# 10_USB_HDMI.net
KiCad netlist of a schematic drawn in Altium Designer
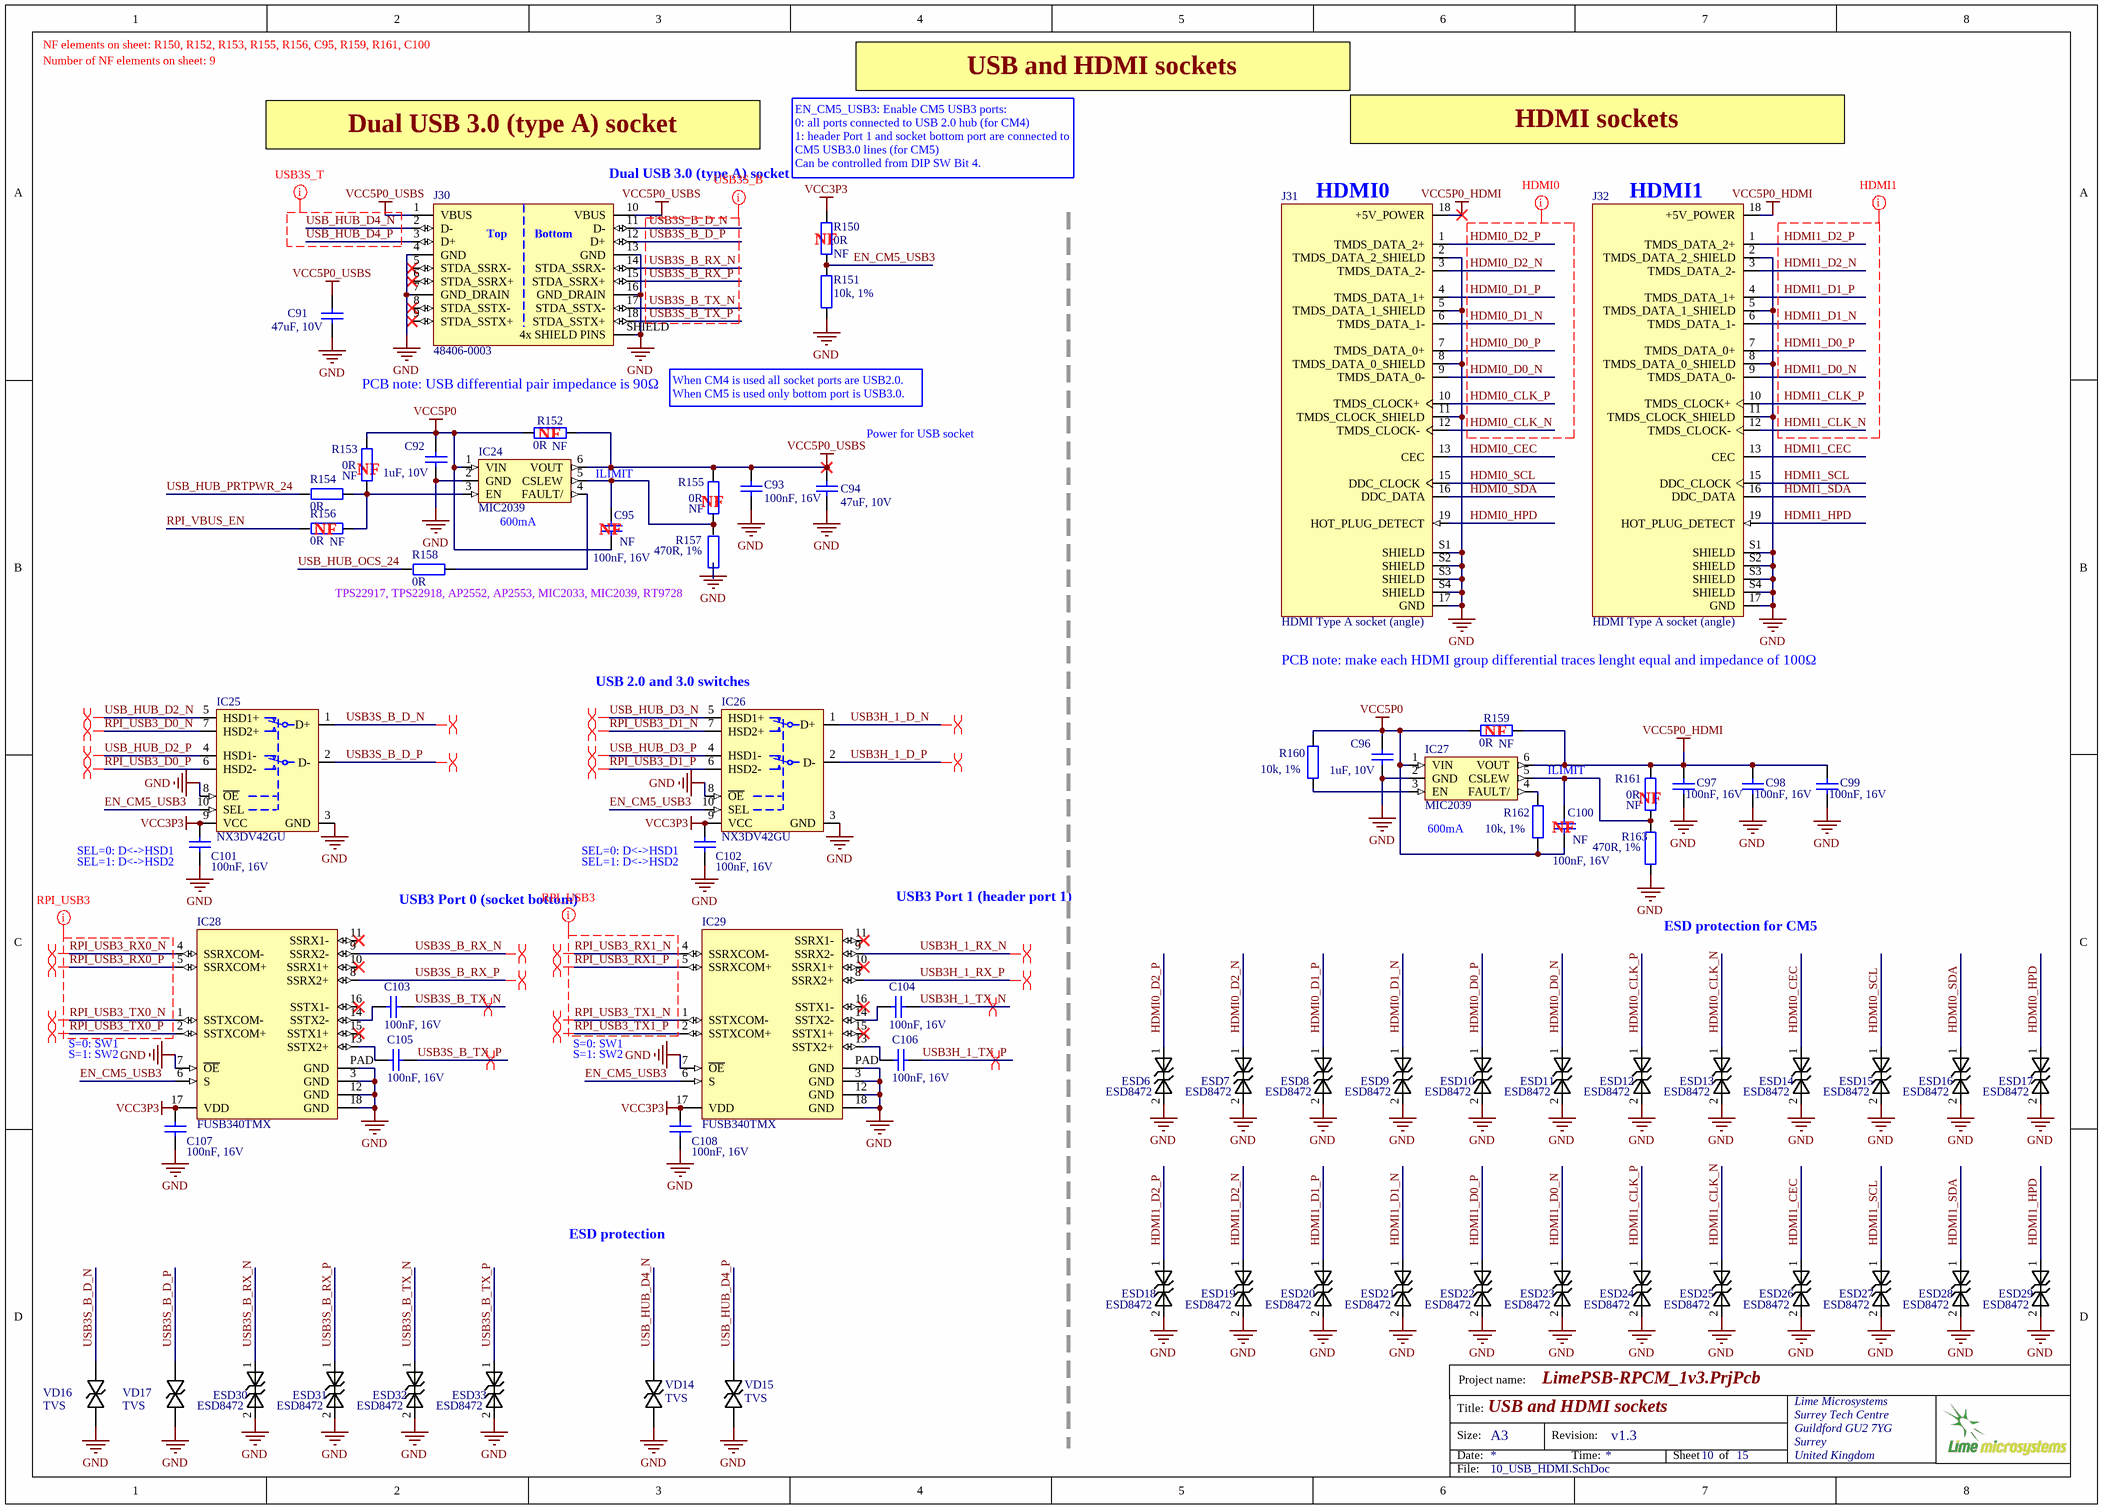
[diagram p0: 10_USB_HDMI.SchDoc]

(export (version "E")
  (design (tool "Eeschema 10.0.6"))
  (components
    (comp (ref "C91")
      (value "47uF, 10V")
      (footprint "CAP1206")
      (fields (field (name "TOLERANCE") "±20%") (field (name "MANUFACTURER") "TDK Corporation"))
      (libsource (lib "LimeFPGAboard_schLib") (part "Cap_1206"))
    )
    (comp (ref "C92")
      (value "1uF, 10V")
      (footprint "CAP0402")
      (fields (field (name "MANUFACTURER") "Yageo"))
      (libsource (lib "LimeMicroAltiumLib_schLib") (part "Cap_0402"))
    )
    (comp (ref "C93")
      (value "100nF, 16V")
      (footprint "CAP0402")
      (fields
        (field (name "MANUFACTURER") "Murata Electronics")
        (field (name "TOLERANCE") "10 %")
        (field (name "MANUFACTURER PART NUMBER") "GRM155R71C104KA88D")
      )
      (libsource (lib "LimeMicroAltiumLib_schLib") (part "Cap_0402"))
    )
    (comp (ref "C94")
      (value "47uF, 10V")
      (footprint "CAP1206")
      (fields (field (name "TOLERANCE") "±20%") (field (name "MANUFACTURER") "TDK Corporation"))
      (libsource (lib "LimeFPGAboard_schLib") (part "Cap_1206"))
    )
    (comp (ref "C95")
      (value "100nF, 16V")
      (footprint "CAP0402")
      (fields
        (field (name "ASSEMBLY INFO") "NF")
        (field (name "MANUFACTURER") "Murata Electronics")
        (field (name "TOLERANCE") "10 %")
        (field (name "MANUFACTURER PART NUMBER") "GRM155R71C104KA88D")
      )
      (libsource (lib "LimeMicroAltiumLib_schLib") (part "Cap_0402"))
    )
    (comp (ref "C96")
      (value "1uF, 10V")
      (footprint "CAP0402")
      (fields (field (name "MANUFACTURER") "Yageo"))
      (libsource (lib "LimeMicroAltiumLib_schLib") (part "Cap_0402"))
    )
    (comp (ref "C97")
      (value "100nF, 16V")
      (footprint "CAP0402")
      (fields
        (field (name "MANUFACTURER") "Murata Electronics")
        (field (name "TOLERANCE") "10 %")
        (field (name "MANUFACTURER PART NUMBER") "GRM155R71C104KA88D")
      )
      (libsource (lib "LimeMicroAltiumLib_schLib") (part "Cap_0402"))
    )
    (comp (ref "C98")
      (value "100nF, 16V")
      (footprint "CAP0402")
      (fields
        (field (name "MANUFACTURER") "Murata Electronics")
        (field (name "TOLERANCE") "10 %")
        (field (name "MANUFACTURER PART NUMBER") "GRM155R71C104KA88D")
      )
      (libsource (lib "LimeMicroAltiumLib_schLib") (part "Cap_0402"))
    )
    (comp (ref "C99")
      (value "100nF, 16V")
      (footprint "CAP0402")
      (fields
        (field (name "MANUFACTURER") "Murata Electronics")
        (field (name "TOLERANCE") "10 %")
        (field (name "MANUFACTURER PART NUMBER") "GRM155R71C104KA88D")
      )
      (libsource (lib "LimeMicroAltiumLib_schLib") (part "Cap_0402"))
    )
    (comp (ref "C100")
      (value "100nF, 16V")
      (footprint "CAP0402")
      (fields
        (field (name "ASSEMBLY INFO") "NF")
        (field (name "MANUFACTURER") "Murata Electronics")
        (field (name "TOLERANCE") "10 %")
        (field (name "MANUFACTURER PART NUMBER") "GRM155R71C104KA88D")
      )
      (libsource (lib "LimeMicroAltiumLib_schLib") (part "Cap_0402"))
    )
    (comp (ref "C101")
      (value "100nF, 16V")
      (footprint "CAP0402")
      (fields
        (field (name "MANUFACTURER") "Murata Electronics")
        (field (name "TOLERANCE") "10 %")
        (field (name "MANUFACTURER PART NUMBER") "GRM155R71C104KA88D")
      )
      (libsource (lib "") (part "Cap_0402_1"))
    )
    (comp (ref "C102")
      (value "100nF, 16V")
      (footprint "CAP0402")
      (fields
        (field (name "MANUFACTURER") "Murata Electronics")
        (field (name "TOLERANCE") "10 %")
        (field (name "MANUFACTURER PART NUMBER") "GRM155R71C104KA88D")
      )
      (libsource (lib "") (part "Cap_0402_1"))
    )
    (comp (ref "C103")
      (value "100nF, 16V")
      (footprint "CAP0402")
      (fields
        (field (name "MANUFACTURER") "Murata Electronics")
        (field (name "TOLERANCE") "10 %")
        (field (name "MANUFACTURER PART NUMBER") "GRM155R71C104KA88D")
      )
      (libsource (lib "") (part "Cap_0402_1"))
    )
    (comp (ref "C104")
      (value "100nF, 16V")
      (footprint "CAP0402")
      (fields
        (field (name "MANUFACTURER") "Murata Electronics")
        (field (name "TOLERANCE") "10 %")
        (field (name "MANUFACTURER PART NUMBER") "GRM155R71C104KA88D")
      )
      (libsource (lib "") (part "Cap_0402_1"))
    )
    (comp (ref "C105")
      (value "100nF, 16V")
      (footprint "CAP0402")
      (fields
        (field (name "MANUFACTURER") "Murata Electronics")
        (field (name "TOLERANCE") "10 %")
        (field (name "MANUFACTURER PART NUMBER") "GRM155R71C104KA88D")
      )
      (libsource (lib "") (part "Cap_0402_1"))
    )
    (comp (ref "C106")
      (value "100nF, 16V")
      (footprint "CAP0402")
      (fields
        (field (name "MANUFACTURER") "Murata Electronics")
        (field (name "TOLERANCE") "10 %")
        (field (name "MANUFACTURER PART NUMBER") "GRM155R71C104KA88D")
      )
      (libsource (lib "") (part "Cap_0402_1"))
    )
    (comp (ref "C107")
      (value "100nF, 16V")
      (footprint "CAP0402")
      (fields
        (field (name "MANUFACTURER") "Murata Electronics")
        (field (name "TOLERANCE") "10 %")
        (field (name "MANUFACTURER PART NUMBER") "GRM155R71C104KA88D")
      )
      (libsource (lib "") (part "Cap_0402_1"))
    )
    (comp (ref "C108")
      (value "100nF, 16V")
      (footprint "CAP0402")
      (fields
        (field (name "MANUFACTURER") "Murata Electronics")
        (field (name "TOLERANCE") "10 %")
        (field (name "MANUFACTURER PART NUMBER") "GRM155R71C104KA88D")
      )
      (libsource (lib "") (part "Cap_0402_1"))
    )
    (comp (ref "ESD6")
      (value "ESD8472")
      (footprint "ESD8472_X3DFN2")
      (fields (field (name "MANUFACTURER") "ON Semiconductor"))
      (libsource (lib "LimeMicroAltiumLib_schLib") (part "ESD8472"))
    )
    (comp (ref "ESD7")
      (value "ESD8472")
      (footprint "ESD8472_X3DFN2")
      (fields (field (name "MANUFACTURER") "ON Semiconductor"))
      (libsource (lib "LimeMicroAltiumLib_schLib") (part "ESD8472"))
    )
    (comp (ref "ESD8")
      (value "ESD8472")
      (footprint "ESD8472_X3DFN2")
      (fields (field (name "MANUFACTURER") "ON Semiconductor"))
      (libsource (lib "LimeMicroAltiumLib_schLib") (part "ESD8472"))
    )
    (comp (ref "ESD9")
      (value "ESD8472")
      (footprint "ESD8472_X3DFN2")
      (fields (field (name "MANUFACTURER") "ON Semiconductor"))
      (libsource (lib "LimeMicroAltiumLib_schLib") (part "ESD8472"))
    )
    (comp (ref "ESD10")
      (value "ESD8472")
      (footprint "ESD8472_X3DFN2")
      (fields (field (name "MANUFACTURER") "ON Semiconductor"))
      (libsource (lib "LimeMicroAltiumLib_schLib") (part "ESD8472"))
    )
    (comp (ref "ESD11")
      (value "ESD8472")
      (footprint "ESD8472_X3DFN2")
      (fields (field (name "MANUFACTURER") "ON Semiconductor"))
      (libsource (lib "LimeMicroAltiumLib_schLib") (part "ESD8472"))
    )
    (comp (ref "ESD12")
      (value "ESD8472")
      (footprint "ESD8472_X3DFN2")
      (fields (field (name "MANUFACTURER") "ON Semiconductor"))
      (libsource (lib "LimeMicroAltiumLib_schLib") (part "ESD8472"))
    )
    (comp (ref "ESD13")
      (value "ESD8472")
      (footprint "ESD8472_X3DFN2")
      (fields (field (name "MANUFACTURER") "ON Semiconductor"))
      (libsource (lib "LimeMicroAltiumLib_schLib") (part "ESD8472"))
    )
    (comp (ref "ESD14")
      (value "ESD8472")
      (footprint "ESD8472_X3DFN2")
      (fields (field (name "MANUFACTURER") "ON Semiconductor"))
      (libsource (lib "LimeMicroAltiumLib_schLib") (part "ESD8472"))
    )
    (comp (ref "ESD15")
      (value "ESD8472")
      (footprint "ESD8472_X3DFN2")
      (fields (field (name "MANUFACTURER") "ON Semiconductor"))
      (libsource (lib "LimeMicroAltiumLib_schLib") (part "ESD8472"))
    )
    (comp (ref "ESD16")
      (value "ESD8472")
      (footprint "ESD8472_X3DFN2")
      (fields (field (name "MANUFACTURER") "ON Semiconductor"))
      (libsource (lib "LimeMicroAltiumLib_schLib") (part "ESD8472"))
    )
    (comp (ref "ESD17")
      (value "ESD8472")
      (footprint "ESD8472_X3DFN2")
      (fields (field (name "MANUFACTURER") "ON Semiconductor"))
      (libsource (lib "LimeMicroAltiumLib_schLib") (part "ESD8472"))
    )
    (comp (ref "ESD18")
      (value "ESD8472")
      (footprint "ESD8472_X3DFN2")
      (fields (field (name "MANUFACTURER") "ON Semiconductor"))
      (libsource (lib "LimeMicroAltiumLib_schLib") (part "ESD8472"))
    )
    (comp (ref "ESD19")
      (value "ESD8472")
      (footprint "ESD8472_X3DFN2")
      (fields (field (name "MANUFACTURER") "ON Semiconductor"))
      (libsource (lib "LimeMicroAltiumLib_schLib") (part "ESD8472"))
    )
    (comp (ref "ESD20")
      (value "ESD8472")
      (footprint "ESD8472_X3DFN2")
      (fields (field (name "MANUFACTURER") "ON Semiconductor"))
      (libsource (lib "LimeMicroAltiumLib_schLib") (part "ESD8472"))
    )
    (comp (ref "ESD21")
      (value "ESD8472")
      (footprint "ESD8472_X3DFN2")
      (fields (field (name "MANUFACTURER") "ON Semiconductor"))
      (libsource (lib "LimeMicroAltiumLib_schLib") (part "ESD8472"))
    )
    (comp (ref "ESD22")
      (value "ESD8472")
      (footprint "ESD8472_X3DFN2")
      (fields (field (name "MANUFACTURER") "ON Semiconductor"))
      (libsource (lib "LimeMicroAltiumLib_schLib") (part "ESD8472"))
    )
    (comp (ref "ESD23")
      (value "ESD8472")
      (footprint "ESD8472_X3DFN2")
      (fields (field (name "MANUFACTURER") "ON Semiconductor"))
      (libsource (lib "LimeMicroAltiumLib_schLib") (part "ESD8472"))
    )
    (comp (ref "ESD24")
      (value "ESD8472")
      (footprint "ESD8472_X3DFN2")
      (fields (field (name "MANUFACTURER") "ON Semiconductor"))
      (libsource (lib "LimeMicroAltiumLib_schLib") (part "ESD8472"))
    )
    (comp (ref "ESD25")
      (value "ESD8472")
      (footprint "ESD8472_X3DFN2")
      (fields (field (name "MANUFACTURER") "ON Semiconductor"))
      (libsource (lib "LimeMicroAltiumLib_schLib") (part "ESD8472"))
    )
    (comp (ref "ESD26")
      (value "ESD8472")
      (footprint "ESD8472_X3DFN2")
      (fields (field (name "MANUFACTURER") "ON Semiconductor"))
      (libsource (lib "LimeMicroAltiumLib_schLib") (part "ESD8472"))
    )
    (comp (ref "ESD27")
      (value "ESD8472")
      (footprint "ESD8472_X3DFN2")
      (fields (field (name "MANUFACTURER") "ON Semiconductor"))
      (libsource (lib "LimeMicroAltiumLib_schLib") (part "ESD8472"))
    )
    (comp (ref "ESD28")
      (value "ESD8472")
      (footprint "ESD8472_X3DFN2")
      (fields (field (name "MANUFACTURER") "ON Semiconductor"))
      (libsource (lib "LimeMicroAltiumLib_schLib") (part "ESD8472"))
    )
    (comp (ref "ESD29")
      (value "ESD8472")
      (footprint "ESD8472_X3DFN2")
      (fields (field (name "MANUFACTURER") "ON Semiconductor"))
      (libsource (lib "LimeMicroAltiumLib_schLib") (part "ESD8472"))
    )
    (comp (ref "ESD30")
      (value "ESD8472")
      (footprint "ESD8472_X3DFN2")
      (fields (field (name "MANUFACTURER") "ON Semiconductor"))
      (libsource (lib "LimeMicroAltiumLib_schLib") (part "ESD8472"))
    )
    (comp (ref "ESD31")
      (value "ESD8472")
      (footprint "ESD8472_X3DFN2")
      (fields (field (name "MANUFACTURER") "ON Semiconductor"))
      (libsource (lib "LimeMicroAltiumLib_schLib") (part "ESD8472"))
    )
    (comp (ref "ESD32")
      (value "ESD8472")
      (footprint "ESD8472_X3DFN2")
      (fields (field (name "MANUFACTURER") "ON Semiconductor"))
      (libsource (lib "LimeMicroAltiumLib_schLib") (part "ESD8472"))
    )
    (comp (ref "ESD33")
      (value "ESD8472")
      (footprint "ESD8472_X3DFN2")
      (fields (field (name "MANUFACTURER") "ON Semiconductor"))
      (libsource (lib "LimeMicroAltiumLib_schLib") (part "ESD8472"))
    )
    (comp (ref "IC24")
      (value "MIC2039")
      (footprint "SOT23-6")
      (fields (field (name "MANUFACTURER") "Microchip"))
      (libsource (lib "LimeMicroAltiumLib_schLib_r04") (part "MIC2033_power_switch"))
    )
    (comp (ref "IC25")
      (value "NX3DV42GU")
      (footprint "FSUSB42UMX")
      (fields (field (name "MANUFACTURER") "NXP Semiconductors"))
      (libsource (lib "LimeMicroAltiumLib_schLib_r01") (part "FSUSB42UMX"))
    )
    (comp (ref "IC26")
      (value "NX3DV42GU")
      (footprint "FSUSB42UMX")
      (fields (field (name "MANUFACTURER") "NXP Semiconductors"))
      (libsource (lib "LimeMicroAltiumLib_schLib_r01") (part "FSUSB42UMX"))
    )
    (comp (ref "IC27")
      (value "MIC2039")
      (footprint "SOT23-6")
      (fields (field (name "MANUFACTURER") "Microchip"))
      (libsource (lib "LimeMicroAltiumLib_schLib_r04") (part "MIC2033_power_switch"))
    )
    (comp (ref "IC28")
      (value "FUSB340TMX")
      (footprint "FUSB340TMX_USB_switch_18-XFQFN")
      (fields (field (name "MANUFACTURER") "ON Semiconductor / Fairchild"))
      (libsource (lib "LimeMicroAltiumLib") (part "FUSB340TMX_USB_switch"))
    )
    (comp (ref "IC29")
      (value "FUSB340TMX")
      (footprint "FUSB340TMX_USB_switch_18-XFQFN")
      (fields (field (name "MANUFACTURER") "ON Semiconductor / Fairchild"))
      (libsource (lib "LimeMicroAltiumLib") (part "FUSB340TMX_USB_switch"))
    )
    (comp (ref "J30")
      (value "48406-0003")
      (footprint "Dual_USB_48406-0003_Molex")
      (fields (field (name "MANUFACTURER") "Molex"))
      (libsource (lib "LimeMicroAltiumLib") (part "Dual_USB_48406-0003_Molex"))
    )
    (comp (ref "J31")
      (value "HDMI Type A socket (angle)")
      (footprint "HDMI_HD01-19-RA-TH")
      (fields (field (name "MANUFACTURER") "CUI Devices"))
      (libsource (lib "LimeMicroAltiumLib_schLib_r04") (part "HDMI_HD01-19-RA-TH"))
    )
    (comp (ref "J32")
      (value "HDMI Type A socket (angle)")
      (footprint "HDMI_HD01-19-RA-TH")
      (fields (field (name "MANUFACTURER") "CUI Devices"))
      (libsource (lib "LimeMicroAltiumLib_schLib_r04") (part "HDMI_HD01-19-RA-TH"))
    )
    (comp (ref "R150")
      (value "0R")
      (footprint "RES0402")
      (fields
        (field (name "ASSEMBLY INFO") "NF")
        (field (name "MANUFACTURER") "Yageo")
        (field (name "TOLERANCE") "Jumper")
      )
      (libsource (lib "") (part "Res_0402_1"))
    )
    (comp (ref "R151")
      (value "10k, 1%")
      (footprint "RES0402")
      (fields (field (name "MANUFACTURER") "Yageo") (field (name "TOLERANCE") "±1%"))
      (libsource (lib "") (part "Res_0402_1"))
    )
    (comp (ref "R152")
      (value "0R")
      (footprint "RES0402")
      (fields
        (field (name "ASSEMBLY INFO") "NF")
        (field (name "MANUFACTURER") "Yageo")
        (field (name "TOLERANCE") "Jumper")
      )
      (libsource (lib "LimeMicroAltiumLib_schLib") (part "Res_0402"))
    )
    (comp (ref "R153")
      (value "0R")
      (footprint "RES0402")
      (fields
        (field (name "ASSEMBLY INFO") "NF")
        (field (name "MANUFACTURER") "Yageo")
        (field (name "TOLERANCE") "Jumper")
      )
      (libsource (lib "LimeMicroAltiumLib_schLib") (part "Res_0402"))
    )
    (comp (ref "R154")
      (value "0R")
      (footprint "RES0402")
      (fields (field (name "MANUFACTURER") "Yageo") (field (name "TOLERANCE") "Jumper"))
      (libsource (lib "LimeMicroAltiumLib_schLib") (part "Res_0402"))
    )
    (comp (ref "R155")
      (value "0R")
      (footprint "RES0402")
      (fields
        (field (name "ASSEMBLY INFO") "NF")
        (field (name "MANUFACTURER") "Yageo")
        (field (name "TOLERANCE") "Jumper")
      )
      (libsource (lib "LimeMicroAltiumLib_schLib") (part "Res_0402"))
    )
    (comp (ref "R156")
      (value "0R")
      (footprint "RES0402")
      (fields
        (field (name "ASSEMBLY INFO") "NF")
        (field (name "MANUFACTURER") "Yageo")
        (field (name "TOLERANCE") "Jumper")
      )
      (libsource (lib "LimeMicroAltiumLib_schLib") (part "Res_0402"))
    )
    (comp (ref "R157")
      (value "470R, 1%")
      (footprint "RES0402")
      (fields (field (name "TOLERANCE") "1%") (field (name "MANUFACTURER") "Yageo"))
      (libsource (lib "LimeMicroAltiumLib_schLib") (part "Res_0402"))
    )
    (comp (ref "R158")
      (value "0R")
      (footprint "RES0402")
      (fields (field (name "MANUFACTURER") "Yageo") (field (name "TOLERANCE") "Jumper"))
      (libsource (lib "LimeMicroAltiumLib_schLib") (part "Res_0402"))
    )
    (comp (ref "R159")
      (value "0R")
      (footprint "RES0402")
      (fields
        (field (name "ASSEMBLY INFO") "NF")
        (field (name "MANUFACTURER") "Yageo")
        (field (name "TOLERANCE") "Jumper")
      )
      (libsource (lib "LimeMicroAltiumLib_schLib") (part "Res_0402"))
    )
    (comp (ref "R160")
      (value "10k, 1%")
      (footprint "RES0402")
      (fields (field (name "MANUFACTURER") "Yageo") (field (name "TOLERANCE") "±1%"))
      (libsource (lib "") (part "Res_0402_1"))
    )
    (comp (ref "R161")
      (value "0R")
      (footprint "RES0402")
      (fields
        (field (name "ASSEMBLY INFO") "NF")
        (field (name "MANUFACTURER") "Yageo")
        (field (name "TOLERANCE") "Jumper")
      )
      (libsource (lib "LimeMicroAltiumLib_schLib") (part "Res_0402"))
    )
    (comp (ref "R162")
      (value "10k, 1%")
      (footprint "RES0402")
      (fields (field (name "MANUFACTURER") "Yageo") (field (name "TOLERANCE") "±1%"))
      (libsource (lib "") (part "Res_0402_1"))
    )
    (comp (ref "R163")
      (value "470R, 1%")
      (footprint "RES0402")
      (fields (field (name "TOLERANCE") "1%") (field (name "MANUFACTURER") "Yageo"))
      (libsource (lib "LimeMicroAltiumLib_schLib") (part "Res_0402"))
    )
    (comp (ref "VD14")
      (value "TVS")
      (footprint "SOD323")
      (fields
        (field (name "MANUFACTURER PART NUMBER") "SD03LCC")
        (field (name "MANUFACTURER") "Sangdest Microelectronics")
      )
      (libsource (lib "LimeNet-Micro_2v1-SDR") (part "DIODE_TVS"))
    )
    (comp (ref "VD15")
      (value "TVS")
      (footprint "SOD323")
      (fields
        (field (name "MANUFACTURER PART NUMBER") "SD03LCC")
        (field (name "MANUFACTURER") "Sangdest Microelectronics")
      )
      (libsource (lib "LimeNet-Micro_2v1-SDR") (part "DIODE_TVS"))
    )
    (comp (ref "VD16")
      (value "TVS")
      (footprint "SOD323")
      (fields
        (field (name "MANUFACTURER PART NUMBER") "SD03LCC")
        (field (name "MANUFACTURER") "Sangdest Microelectronics")
      )
      (libsource (lib "LimeNet-Micro_2v1-SDR") (part "DIODE_TVS"))
    )
    (comp (ref "VD17")
      (value "TVS")
      (footprint "SOD323")
      (fields
        (field (name "MANUFACTURER PART NUMBER") "SD03LCC")
        (field (name "MANUFACTURER") "Sangdest Microelectronics")
      )
      (libsource (lib "LimeNet-Micro_2v1-SDR") (part "DIODE_TVS"))
    )
  )
  (nets
    (net (code "1") (name "/EN_CM5_USB3") (class "Default")
      (node (ref "IC25") (pin "10") (pinfunction "SEL_10") (pintype "input"))
      (node (ref "IC26") (pin "10") (pinfunction "SEL_10") (pintype "input"))
      (node (ref "IC28") (pin "6") (pinfunction "S_6") (pintype "input"))
      (node (ref "IC29") (pin "6") (pinfunction "S_6") (pintype "input"))
      (node (ref "R150") (pin "1") (pinfunction "1_1") (pintype "passive"))
      (node (ref "R151") (pin "1") (pinfunction "1_1") (pintype "passive"))
    )
    (net (code "2") (name "/HDMI0_CEC") (class "Default")
      (node (ref "ESD14") (pin "1") (pinfunction "1_1") (pintype "passive"))
      (node (ref "J31") (pin "13") (pinfunction "CEC_13") (pintype "bidirectional"))
    )
    (net (code "3") (name "/HDMI0_CLK_N") (class "Default")
      (node (ref "ESD13") (pin "1") (pinfunction "1_1") (pintype "passive"))
      (node (ref "J31") (pin "12") (pinfunction "TMDS_CLOCK-_12") (pintype "bidirectional"))
    )
    (net (code "4") (name "/HDMI0_CLK_P") (class "Default")
      (node (ref "ESD12") (pin "1") (pinfunction "1_1") (pintype "passive"))
      (node (ref "J31") (pin "10") (pinfunction "TMDS_CLOCK+_10") (pintype "bidirectional"))
    )
    (net (code "5") (name "/HDMI0_D0_N") (class "Default")
      (node (ref "ESD11") (pin "1") (pinfunction "1_1") (pintype "passive"))
      (node (ref "J31") (pin "9") (pinfunction "TMDS_DATA_0-_9") (pintype "bidirectional"))
    )
    (net (code "6") (name "/HDMI0_D0_P") (class "Default")
      (node (ref "ESD10") (pin "1") (pinfunction "1_1") (pintype "passive"))
      (node (ref "J31") (pin "7") (pinfunction "TMDS_DATA_0+_7") (pintype "bidirectional"))
    )
    (net (code "7") (name "/HDMI0_D1_N") (class "Default")
      (node (ref "ESD9") (pin "1") (pinfunction "1_1") (pintype "passive"))
      (node (ref "J31") (pin "6") (pinfunction "TMDS_DATA_1-_6") (pintype "bidirectional"))
    )
    (net (code "8") (name "/HDMI0_D1_P") (class "Default")
      (node (ref "ESD8") (pin "1") (pinfunction "1_1") (pintype "passive"))
      (node (ref "J31") (pin "4") (pinfunction "TMDS_DATA_1+_4") (pintype "bidirectional"))
    )
    (net (code "9") (name "/HDMI0_D2_N") (class "Default")
      (node (ref "ESD7") (pin "1") (pinfunction "1_1") (pintype "passive"))
      (node (ref "J31") (pin "3") (pinfunction "TMDS_DATA_2-_3") (pintype "bidirectional"))
    )
    (net (code "10") (name "/HDMI0_D2_P") (class "Default")
      (node (ref "ESD6") (pin "1") (pinfunction "1_1") (pintype "passive"))
      (node (ref "J31") (pin "1") (pinfunction "TMDS_DATA_2+_1") (pintype "bidirectional"))
    )
    (net (code "11") (name "/HDMI0_HPD") (class "Default")
      (node (ref "ESD17") (pin "1") (pinfunction "1_1") (pintype "passive"))
      (node (ref "J31") (pin "19") (pinfunction "HOT_PLUG_DETECT_19") (pintype "input"))
    )
    (net (code "12") (name "/HDMI0_SCL") (class "Default")
      (node (ref "ESD15") (pin "1") (pinfunction "1_1") (pintype "passive"))
      (node (ref "J31") (pin "15") (pinfunction "DDC_CLOCK_15") (pintype "bidirectional"))
    )
    (net (code "13") (name "/HDMI0_SDA") (class "Default")
      (node (ref "ESD16") (pin "1") (pinfunction "1_1") (pintype "passive"))
      (node (ref "J31") (pin "16") (pinfunction "DDC_DATA_16") (pintype "bidirectional"))
    )
    (net (code "14") (name "/HDMI1_CEC") (class "Default")
      (node (ref "ESD26") (pin "1") (pinfunction "1_1") (pintype "passive"))
      (node (ref "J32") (pin "13") (pinfunction "CEC_13") (pintype "bidirectional"))
    )
    (net (code "15") (name "/HDMI1_CLK_N") (class "Default")
      (node (ref "ESD25") (pin "1") (pinfunction "1_1") (pintype "passive"))
      (node (ref "J32") (pin "12") (pinfunction "TMDS_CLOCK-_12") (pintype "bidirectional"))
    )
    (net (code "16") (name "/HDMI1_CLK_P") (class "Default")
      (node (ref "ESD24") (pin "1") (pinfunction "1_1") (pintype "passive"))
      (node (ref "J32") (pin "10") (pinfunction "TMDS_CLOCK+_10") (pintype "bidirectional"))
    )
    (net (code "17") (name "/HDMI1_D0_N") (class "Default")
      (node (ref "ESD23") (pin "1") (pinfunction "1_1") (pintype "passive"))
      (node (ref "J32") (pin "9") (pinfunction "TMDS_DATA_0-_9") (pintype "bidirectional"))
    )
    (net (code "18") (name "/HDMI1_D0_P") (class "Default")
      (node (ref "ESD22") (pin "1") (pinfunction "1_1") (pintype "passive"))
      (node (ref "J32") (pin "7") (pinfunction "TMDS_DATA_0+_7") (pintype "bidirectional"))
    )
    (net (code "19") (name "/HDMI1_D1_N") (class "Default")
      (node (ref "ESD21") (pin "1") (pinfunction "1_1") (pintype "passive"))
      (node (ref "J32") (pin "6") (pinfunction "TMDS_DATA_1-_6") (pintype "bidirectional"))
    )
    (net (code "20") (name "/HDMI1_D1_P") (class "Default")
      (node (ref "ESD20") (pin "1") (pinfunction "1_1") (pintype "passive"))
      (node (ref "J32") (pin "4") (pinfunction "TMDS_DATA_1+_4") (pintype "bidirectional"))
    )
    (net (code "21") (name "/HDMI1_D2_N") (class "Default")
      (node (ref "ESD19") (pin "1") (pinfunction "1_1") (pintype "passive"))
      (node (ref "J32") (pin "3") (pinfunction "TMDS_DATA_2-_3") (pintype "bidirectional"))
    )
    (net (code "22") (name "/HDMI1_D2_P") (class "Default")
      (node (ref "ESD18") (pin "1") (pinfunction "1_1") (pintype "passive"))
      (node (ref "J32") (pin "1") (pinfunction "TMDS_DATA_2+_1") (pintype "bidirectional"))
    )
    (net (code "23") (name "/HDMI1_HPD") (class "Default")
      (node (ref "ESD29") (pin "1") (pinfunction "1_1") (pintype "passive"))
      (node (ref "J32") (pin "19") (pinfunction "HOT_PLUG_DETECT_19") (pintype "input"))
    )
    (net (code "24") (name "/HDMI1_SCL") (class "Default")
      (node (ref "ESD27") (pin "1") (pinfunction "1_1") (pintype "passive"))
      (node (ref "J32") (pin "15") (pinfunction "DDC_CLOCK_15") (pintype "bidirectional"))
    )
    (net (code "25") (name "/HDMI1_SDA") (class "Default")
      (node (ref "ESD28") (pin "1") (pinfunction "1_1") (pintype "passive"))
      (node (ref "J32") (pin "16") (pinfunction "DDC_DATA_16") (pintype "bidirectional"))
    )
    (net (code "26") (name "/RPI_USB3_D0_N") (class "Default")
      (node (ref "IC25") (pin "7") (pinfunction "HSD2+_7") (pintype "passive"))
    )
    (net (code "27") (name "/RPI_USB3_D0_P") (class "Default")
      (node (ref "IC25") (pin "6") (pinfunction "HSD2-_6") (pintype "passive"))
    )
    (net (code "28") (name "/RPI_USB3_D1_N") (class "Default")
      (node (ref "IC26") (pin "7") (pinfunction "HSD2+_7") (pintype "passive"))
    )
    (net (code "29") (name "/RPI_USB3_D1_P") (class "Default")
      (node (ref "IC26") (pin "6") (pinfunction "HSD2-_6") (pintype "passive"))
    )
    (net (code "30") (name "/RPI_USB3_RX0_N") (class "Default")
      (node (ref "IC28") (pin "4") (pinfunction "SSRXCOM-_4") (pintype "bidirectional"))
    )
    (net (code "31") (name "/RPI_USB3_RX0_P") (class "Default")
      (node (ref "IC28") (pin "5") (pinfunction "SSRXCOM+_5") (pintype "bidirectional"))
    )
    (net (code "32") (name "/RPI_USB3_RX1_N") (class "Default")
      (node (ref "IC29") (pin "4") (pinfunction "SSRXCOM-_4") (pintype "bidirectional"))
    )
    (net (code "33") (name "/RPI_USB3_RX1_P") (class "Default")
      (node (ref "IC29") (pin "5") (pinfunction "SSRXCOM+_5") (pintype "bidirectional"))
    )
    (net (code "34") (name "/RPI_USB3_TX0_N") (class "Default")
      (node (ref "IC28") (pin "1") (pinfunction "SSTXCOM-_1") (pintype "bidirectional"))
    )
    (net (code "35") (name "/RPI_USB3_TX0_P") (class "Default")
      (node (ref "IC28") (pin "2") (pinfunction "SSTXCOM+_2") (pintype "bidirectional"))
    )
    (net (code "36") (name "/RPI_USB3_TX1_N") (class "Default")
      (node (ref "IC29") (pin "1") (pinfunction "SSTXCOM-_1") (pintype "bidirectional"))
    )
    (net (code "37") (name "/RPI_USB3_TX1_P") (class "Default")
      (node (ref "IC29") (pin "2") (pinfunction "SSTXCOM+_2") (pintype "bidirectional"))
    )
    (net (code "38") (name "/RPI_VBUS_EN") (class "Default")
      (node (ref "R156") (pin "2") (pinfunction "2_2") (pintype "passive"))
    )
    (net (code "39") (name "/USB3H_1_D_N") (class "Default")
      (node (ref "IC26") (pin "1") (pinfunction "D+_1") (pintype "passive"))
    )
    (net (code "40") (name "/USB3H_1_D_P") (class "Default")
      (node (ref "IC26") (pin "2") (pinfunction "D-_2") (pintype "passive"))
    )
    (net (code "41") (name "/USB3H_1_RX_N") (class "Default")
      (node (ref "IC29") (pin "9") (pinfunction "SSRX2-_9") (pintype "bidirectional"))
    )
    (net (code "42") (name "/USB3H_1_RX_P") (class "Default")
      (node (ref "IC29") (pin "8") (pinfunction "SSRX2+_8") (pintype "bidirectional"))
    )
    (net (code "43") (name "/USB3H_1_TX_N") (class "Default")
      (node (ref "C104") (pin "2") (pinfunction "2_2") (pintype "passive"))
    )
    (net (code "44") (name "/USB3H_1_TX_P") (class "Default")
      (node (ref "C106") (pin "2") (pinfunction "2_2") (pintype "passive"))
    )
    (net (code "45") (name "/USB3S_B_D_N") (class "Default")
      (node (ref "IC25") (pin "1") (pinfunction "D+_1") (pintype "passive"))
      (node (ref "J30") (pin "11") (pinfunction "D-_11") (pintype "bidirectional"))
      (node (ref "VD16") (pin "A") (pinfunction "A_A") (pintype "passive"))
    )
    (net (code "46") (name "/USB3S_B_D_P") (class "Default")
      (node (ref "IC25") (pin "2") (pinfunction "D-_2") (pintype "passive"))
      (node (ref "J30") (pin "12") (pinfunction "D+_12") (pintype "bidirectional"))
      (node (ref "VD17") (pin "A") (pinfunction "A_A") (pintype "passive"))
    )
    (net (code "47") (name "/USB3S_B_RX_N") (class "Default")
      (node (ref "ESD30") (pin "1") (pinfunction "1_1") (pintype "passive"))
      (node (ref "IC28") (pin "9") (pinfunction "SSRX2-_9") (pintype "bidirectional"))
      (node (ref "J30") (pin "14") (pinfunction "STDA_SSRX-_14") (pintype "bidirectional"))
    )
    (net (code "48") (name "/USB3S_B_RX_P") (class "Default")
      (node (ref "ESD31") (pin "1") (pinfunction "1_1") (pintype "passive"))
      (node (ref "IC28") (pin "8") (pinfunction "SSRX2+_8") (pintype "bidirectional"))
      (node (ref "J30") (pin "15") (pinfunction "STDA_SSRX+_15") (pintype "bidirectional"))
    )
    (net (code "49") (name "/USB3S_B_TX_N") (class "Default")
      (node (ref "C103") (pin "2") (pinfunction "2_2") (pintype "passive"))
      (node (ref "ESD32") (pin "1") (pinfunction "1_1") (pintype "passive"))
      (node (ref "J30") (pin "17") (pinfunction "STDA_SSTX-_17") (pintype "bidirectional"))
    )
    (net (code "50") (name "/USB3S_B_TX_P") (class "Default")
      (node (ref "C105") (pin "2") (pinfunction "2_2") (pintype "passive"))
      (node (ref "ESD33") (pin "1") (pinfunction "1_1") (pintype "passive"))
      (node (ref "J30") (pin "18") (pinfunction "STDA_SSTX+_18") (pintype "bidirectional"))
    )
    (net (code "51") (name "/USB_HUB_D2_N") (class "Default")
      (node (ref "IC25") (pin "5") (pinfunction "HSD1+_5") (pintype "passive"))
    )
    (net (code "52") (name "/USB_HUB_D2_P") (class "Default")
      (node (ref "IC25") (pin "4") (pinfunction "HSD1-_4") (pintype "passive"))
    )
    (net (code "53") (name "/USB_HUB_D3_N") (class "Default")
      (node (ref "IC26") (pin "5") (pinfunction "HSD1+_5") (pintype "passive"))
    )
    (net (code "54") (name "/USB_HUB_D3_P") (class "Default")
      (node (ref "IC26") (pin "4") (pinfunction "HSD1-_4") (pintype "passive"))
    )
    (net (code "55") (name "/USB_HUB_D4_N") (class "Default")
      (node (ref "J30") (pin "2") (pinfunction "D-_2") (pintype "bidirectional"))
      (node (ref "VD14") (pin "A") (pinfunction "A_A") (pintype "passive"))
    )
    (net (code "56") (name "/USB_HUB_D4_P") (class "Default")
      (node (ref "J30") (pin "3") (pinfunction "D+_3") (pintype "bidirectional"))
      (node (ref "VD15") (pin "A") (pinfunction "A_A") (pintype "passive"))
    )
    (net (code "57") (name "/USB_HUB_OCS_24") (class "Default")
      (node (ref "R158") (pin "2") (pinfunction "2_2") (pintype "passive"))
    )
    (net (code "58") (name "/USB_HUB_PRTPWR_24") (class "Default")
      (node (ref "R154") (pin "2") (pinfunction "2_2") (pintype "passive"))
    )
    (net (code "59") (name "GND") (class "Default")
      (node (ref "C101") (pin "2") (pinfunction "2_2") (pintype "passive"))
      (node (ref "C102") (pin "2") (pinfunction "2_2") (pintype "passive"))
      (node (ref "C107") (pin "2") (pinfunction "2_2") (pintype "passive"))
      (node (ref "C108") (pin "2") (pinfunction "2_2") (pintype "passive"))
      (node (ref "C91") (pin "1") (pinfunction "1_1") (pintype "passive"))
      (node (ref "C92") (pin "2") (pinfunction "2_2") (pintype "passive"))
      (node (ref "C93") (pin "2") (pinfunction "2_2") (pintype "passive"))
      (node (ref "C94") (pin "1") (pinfunction "1_1") (pintype "passive"))
      (node (ref "C96") (pin "2") (pinfunction "2_2") (pintype "passive"))
      (node (ref "C97") (pin "2") (pinfunction "2_2") (pintype "passive"))
      (node (ref "C98") (pin "2") (pinfunction "2_2") (pintype "passive"))
      (node (ref "C99") (pin "2") (pinfunction "2_2") (pintype "passive"))
      (node (ref "ESD10") (pin "2") (pinfunction "2_2") (pintype "passive"))
      (node (ref "ESD11") (pin "2") (pinfunction "2_2") (pintype "passive"))
      (node (ref "ESD12") (pin "2") (pinfunction "2_2") (pintype "passive"))
      (node (ref "ESD13") (pin "2") (pinfunction "2_2") (pintype "passive"))
      (node (ref "ESD14") (pin "2") (pinfunction "2_2") (pintype "passive"))
      (node (ref "ESD15") (pin "2") (pinfunction "2_2") (pintype "passive"))
      (node (ref "ESD16") (pin "2") (pinfunction "2_2") (pintype "passive"))
      (node (ref "ESD17") (pin "2") (pinfunction "2_2") (pintype "passive"))
      (node (ref "ESD18") (pin "2") (pinfunction "2_2") (pintype "passive"))
      (node (ref "ESD19") (pin "2") (pinfunction "2_2") (pintype "passive"))
      (node (ref "ESD20") (pin "2") (pinfunction "2_2") (pintype "passive"))
      (node (ref "ESD21") (pin "2") (pinfunction "2_2") (pintype "passive"))
      (node (ref "ESD22") (pin "2") (pinfunction "2_2") (pintype "passive"))
      (node (ref "ESD23") (pin "2") (pinfunction "2_2") (pintype "passive"))
      (node (ref "ESD24") (pin "2") (pinfunction "2_2") (pintype "passive"))
      (node (ref "ESD25") (pin "2") (pinfunction "2_2") (pintype "passive"))
      (node (ref "ESD26") (pin "2") (pinfunction "2_2") (pintype "passive"))
      (node (ref "ESD27") (pin "2") (pinfunction "2_2") (pintype "passive"))
      (node (ref "ESD28") (pin "2") (pinfunction "2_2") (pintype "passive"))
      (node (ref "ESD29") (pin "2") (pinfunction "2_2") (pintype "passive"))
      (node (ref "ESD30") (pin "2") (pinfunction "2_2") (pintype "passive"))
      (node (ref "ESD31") (pin "2") (pinfunction "2_2") (pintype "passive"))
      (node (ref "ESD32") (pin "2") (pinfunction "2_2") (pintype "passive"))
      (node (ref "ESD33") (pin "2") (pinfunction "2_2") (pintype "passive"))
      (node (ref "ESD6") (pin "2") (pinfunction "2_2") (pintype "passive"))
      (node (ref "ESD7") (pin "2") (pinfunction "2_2") (pintype "passive"))
      (node (ref "ESD8") (pin "2") (pinfunction "2_2") (pintype "passive"))
      (node (ref "ESD9") (pin "2") (pinfunction "2_2") (pintype "passive"))
      (node (ref "IC24") (pin "2") (pinfunction "GND_2") (pintype "passive"))
      (node (ref "IC25") (pin "3") (pinfunction "GND_3") (pintype "passive"))
      (node (ref "IC25") (pin "8") (pinfunction "~{OE}_8") (pintype "input"))
      (node (ref "IC26") (pin "3") (pinfunction "GND_3") (pintype "passive"))
      (node (ref "IC26") (pin "8") (pinfunction "~{OE}_8") (pintype "input"))
      (node (ref "IC27") (pin "2") (pinfunction "GND_2") (pintype "passive"))
      (node (ref "IC28") (pin "12") (pinfunction "GND_12") (pintype "passive"))
      (node (ref "IC28") (pin "18") (pinfunction "GND_18") (pintype "passive"))
      (node (ref "IC28") (pin "3") (pinfunction "GND_3") (pintype "passive"))
      (node (ref "IC28") (pin "7") (pinfunction "~{OE}_7") (pintype "input"))
      (node (ref "IC28") (pin "PAD") (pinfunction "GND_PAD") (pintype "passive"))
      (node (ref "IC29") (pin "12") (pinfunction "GND_12") (pintype "passive"))
      (node (ref "IC29") (pin "18") (pinfunction "GND_18") (pintype "passive"))
      (node (ref "IC29") (pin "3") (pinfunction "GND_3") (pintype "passive"))
      (node (ref "IC29") (pin "7") (pinfunction "~{OE}_7") (pintype "input"))
      (node (ref "IC29") (pin "PAD") (pinfunction "GND_PAD") (pintype "passive"))
      (node (ref "J30") (pin "13") (pinfunction "GND_13") (pintype "passive"))
      (node (ref "J30") (pin "16") (pinfunction "GND_DRAIN_16") (pintype "passive"))
      (node (ref "J30") (pin "4") (pinfunction "GND_4") (pintype "passive"))
      (node (ref "J30") (pin "7") (pinfunction "GND_DRAIN_7") (pintype "passive"))
      (node (ref "J30") (pin "SHIELD") (pinfunction "4x_SHIELD_PINS_SHIELD") (pintype "passive"))
      (node (ref "J31") (pin "11") (pinfunction "TMDS_CLOCK_SHIELD_11") (pintype "passive"))
      (node (ref "J31") (pin "17") (pinfunction "GND_17") (pintype "power_in"))
      (node (ref "J31") (pin "2") (pinfunction "TMDS_DATA_2_SHIELD_2") (pintype "passive"))
      (node (ref "J31") (pin "5") (pinfunction "TMDS_DATA_1_SHIELD_5") (pintype "passive"))
      (node (ref "J31") (pin "8") (pinfunction "TMDS_DATA_0_SHIELD_8") (pintype "passive"))
      (node (ref "J31") (pin "S1") (pinfunction "SHIELD_S1") (pintype "passive"))
      (node (ref "J31") (pin "S2") (pinfunction "SHIELD_S2") (pintype "passive"))
      (node (ref "J31") (pin "S3") (pinfunction "SHIELD_S3") (pintype "passive"))
      (node (ref "J31") (pin "S4") (pinfunction "SHIELD_S4") (pintype "passive"))
      (node (ref "J32") (pin "11") (pinfunction "TMDS_CLOCK_SHIELD_11") (pintype "passive"))
      (node (ref "J32") (pin "17") (pinfunction "GND_17") (pintype "power_in"))
      (node (ref "J32") (pin "2") (pinfunction "TMDS_DATA_2_SHIELD_2") (pintype "passive"))
      (node (ref "J32") (pin "5") (pinfunction "TMDS_DATA_1_SHIELD_5") (pintype "passive"))
      (node (ref "J32") (pin "8") (pinfunction "TMDS_DATA_0_SHIELD_8") (pintype "passive"))
      (node (ref "J32") (pin "S1") (pinfunction "SHIELD_S1") (pintype "passive"))
      (node (ref "J32") (pin "S2") (pinfunction "SHIELD_S2") (pintype "passive"))
      (node (ref "J32") (pin "S3") (pinfunction "SHIELD_S3") (pintype "passive"))
      (node (ref "J32") (pin "S4") (pinfunction "SHIELD_S4") (pintype "passive"))
      (node (ref "R151") (pin "2") (pinfunction "2_2") (pintype "passive"))
      (node (ref "R157") (pin "1") (pinfunction "1_1") (pintype "passive"))
      (node (ref "R163") (pin "1") (pinfunction "1_1") (pintype "passive"))
      (node (ref "VD14") (pin "K") (pinfunction "K_K") (pintype "passive"))
      (node (ref "VD15") (pin "K") (pinfunction "K_K") (pintype "passive"))
      (node (ref "VD16") (pin "K") (pinfunction "K_K") (pintype "passive"))
      (node (ref "VD17") (pin "K") (pinfunction "K_K") (pintype "passive"))
    )
    (net (code "60") (name "Net-(IC24-CSLEW)") (class "Default")
      (node (ref "C95") (pin "1") (pinfunction "1_1") (pintype "passive"))
      (node (ref "IC24") (pin "5") (pinfunction "CSLEW_5") (pintype "output"))
      (node (ref "R155") (pin "1") (pinfunction "1_1") (pintype "passive"))
      (node (ref "R157") (pin "2") (pinfunction "2_2") (pintype "passive"))
    )
    (net (code "61") (name "Net-(IC24-EN)") (class "Default")
      (node (ref "IC24") (pin "3") (pinfunction "EN_3") (pintype "input"))
      (node (ref "R153") (pin "1") (pinfunction "1_1") (pintype "passive"))
      (node (ref "R154") (pin "1") (pinfunction "1_1") (pintype "passive"))
      (node (ref "R156") (pin "1") (pinfunction "1_1") (pintype "passive"))
    )
    (net (code "62") (name "Net-(IC24-FAULT{slash})") (class "Default")
      (node (ref "IC24") (pin "4") (pinfunction "FAULT/_4") (pintype "output"))
      (node (ref "R158") (pin "1") (pinfunction "1_1") (pintype "passive"))
    )
    (net (code "63") (name "Net-(IC27-CSLEW)") (class "Default")
      (node (ref "C100") (pin "1") (pinfunction "1_1") (pintype "passive"))
      (node (ref "IC27") (pin "5") (pinfunction "CSLEW_5") (pintype "output"))
      (node (ref "R161") (pin "1") (pinfunction "1_1") (pintype "passive"))
      (node (ref "R163") (pin "2") (pinfunction "2_2") (pintype "passive"))
    )
    (net (code "64") (name "Net-(IC27-EN)") (class "Default")
      (node (ref "IC27") (pin "3") (pinfunction "EN_3") (pintype "input"))
      (node (ref "R160") (pin "1") (pinfunction "1_1") (pintype "passive"))
    )
    (net (code "65") (name "Net-(IC27-FAULT{slash})") (class "Default")
      (node (ref "IC27") (pin "4") (pinfunction "FAULT/_4") (pintype "output"))
      (node (ref "R162") (pin "2") (pinfunction "2_2") (pintype "passive"))
    )
    (net (code "66") (name "Net-(IC28-SSTX2+)") (class "Default")
      (node (ref "C105") (pin "1") (pinfunction "1_1") (pintype "passive"))
      (node (ref "IC28") (pin "13") (pinfunction "SSTX2+_13") (pintype "bidirectional"))
    )
    (net (code "67") (name "Net-(IC28-SSTX2-)") (class "Default")
      (node (ref "C103") (pin "1") (pinfunction "1_1") (pintype "passive"))
      (node (ref "IC28") (pin "14") (pinfunction "SSTX2-_14") (pintype "bidirectional"))
    )
    (net (code "68") (name "Net-(IC29-SSTX2+)") (class "Default")
      (node (ref "C106") (pin "1") (pinfunction "1_1") (pintype "passive"))
      (node (ref "IC29") (pin "13") (pinfunction "SSTX2+_13") (pintype "bidirectional"))
    )
    (net (code "69") (name "Net-(IC29-SSTX2-)") (class "Default")
      (node (ref "C104") (pin "1") (pinfunction "1_1") (pintype "passive"))
      (node (ref "IC29") (pin "14") (pinfunction "SSTX2-_14") (pintype "bidirectional"))
    )
    (net (code "70") (name "VCC3P3") (class "Default")
      (node (ref "C101") (pin "1") (pinfunction "1_1") (pintype "passive"))
      (node (ref "C102") (pin "1") (pinfunction "1_1") (pintype "passive"))
      (node (ref "C107") (pin "1") (pinfunction "1_1") (pintype "passive"))
      (node (ref "C108") (pin "1") (pinfunction "1_1") (pintype "passive"))
      (node (ref "IC25") (pin "9") (pinfunction "VCC_9") (pintype "power_in"))
      (node (ref "IC26") (pin "9") (pinfunction "VCC_9") (pintype "power_in"))
      (node (ref "IC28") (pin "17") (pinfunction "VDD_17") (pintype "power_in"))
      (node (ref "IC29") (pin "17") (pinfunction "VDD_17") (pintype "power_in"))
      (node (ref "R150") (pin "2") (pinfunction "2_2") (pintype "passive"))
    )
    (net (code "71") (name "VCC5P0") (class "Default")
      (node (ref "C100") (pin "2") (pinfunction "2_2") (pintype "passive"))
      (node (ref "C92") (pin "1") (pinfunction "1_1") (pintype "passive"))
      (node (ref "C95") (pin "2") (pinfunction "2_2") (pintype "passive"))
      (node (ref "C96") (pin "1") (pinfunction "1_1") (pintype "passive"))
      (node (ref "IC24") (pin "1") (pinfunction "VIN_1") (pintype "input"))
      (node (ref "IC27") (pin "1") (pinfunction "VIN_1") (pintype "input"))
      (node (ref "R152") (pin "2") (pinfunction "2_2") (pintype "passive"))
      (node (ref "R153") (pin "2") (pinfunction "2_2") (pintype "passive"))
      (node (ref "R159") (pin "2") (pinfunction "2_2") (pintype "passive"))
      (node (ref "R160") (pin "2") (pinfunction "2_2") (pintype "passive"))
      (node (ref "R162") (pin "1") (pinfunction "1_1") (pintype "passive"))
    )
    (net (code "72") (name "VCC5P0_HDMI") (class "Default")
      (node (ref "C97") (pin "1") (pinfunction "1_1") (pintype "passive"))
      (node (ref "C98") (pin "1") (pinfunction "1_1") (pintype "passive"))
      (node (ref "C99") (pin "1") (pinfunction "1_1") (pintype "passive"))
      (node (ref "IC27") (pin "6") (pinfunction "VOUT_6") (pintype "output"))
      (node (ref "J31") (pin "18") (pinfunction "+5V_POWER_18") (pintype "power_in"))
      (node (ref "J32") (pin "18") (pinfunction "+5V_POWER_18") (pintype "power_in"))
      (node (ref "R159") (pin "1") (pinfunction "1_1") (pintype "passive"))
      (node (ref "R161") (pin "2") (pinfunction "2_2") (pintype "passive"))
    )
    (net (code "73") (name "VCC5P0_USBS") (class "Default")
      (node (ref "C91") (pin "2") (pinfunction "2_2") (pintype "passive"))
      (node (ref "C93") (pin "1") (pinfunction "1_1") (pintype "passive"))
      (node (ref "C94") (pin "2") (pinfunction "2_2") (pintype "passive"))
      (node (ref "IC24") (pin "6") (pinfunction "VOUT_6") (pintype "output"))
      (node (ref "J30") (pin "1") (pinfunction "VBUS_1") (pintype "power_in"))
      (node (ref "J30") (pin "10") (pinfunction "VBUS_10") (pintype "power_in"))
      (node (ref "R152") (pin "1") (pinfunction "1_1") (pintype "passive"))
      (node (ref "R155") (pin "2") (pinfunction "2_2") (pintype "passive"))
    )
    (net (code "74") (name "unconnected-(IC28-SSRX1+-Pad10)") (class "Default")
      (node (ref "IC28") (pin "10") (pinfunction "SSRX1+_10") (pintype "bidirectional+no_connect"))
    )
    (net (code "75") (name "unconnected-(IC28-SSRX1--Pad11)") (class "Default")
      (node (ref "IC28") (pin "11") (pinfunction "SSRX1-_11") (pintype "bidirectional+no_connect"))
    )
    (net (code "76") (name "unconnected-(IC28-SSTX1+-Pad15)") (class "Default")
      (node (ref "IC28") (pin "15") (pinfunction "SSTX1+_15") (pintype "bidirectional+no_connect"))
    )
    (net (code "77") (name "unconnected-(IC28-SSTX1--Pad16)") (class "Default")
      (node (ref "IC28") (pin "16") (pinfunction "SSTX1-_16") (pintype "bidirectional+no_connect"))
    )
    (net (code "78") (name "unconnected-(IC29-SSRX1+-Pad10)") (class "Default")
      (node (ref "IC29") (pin "10") (pinfunction "SSRX1+_10") (pintype "bidirectional+no_connect"))
    )
    (net (code "79") (name "unconnected-(IC29-SSRX1--Pad11)") (class "Default")
      (node (ref "IC29") (pin "11") (pinfunction "SSRX1-_11") (pintype "bidirectional+no_connect"))
    )
    (net (code "80") (name "unconnected-(IC29-SSTX1+-Pad15)") (class "Default")
      (node (ref "IC29") (pin "15") (pinfunction "SSTX1+_15") (pintype "bidirectional+no_connect"))
    )
    (net (code "81") (name "unconnected-(IC29-SSTX1--Pad16)") (class "Default")
      (node (ref "IC29") (pin "16") (pinfunction "SSTX1-_16") (pintype "bidirectional+no_connect"))
    )
    (net (code "82") (name "unconnected-(J30-STDA_SSRX+-Pad6)") (class "Default")
      (node (ref "J30") (pin "6") (pinfunction "STDA_SSRX+_6") (pintype "bidirectional+no_connect"))
    )
    (net (code "83") (name "unconnected-(J30-STDA_SSRX--Pad5)") (class "Default")
      (node (ref "J30") (pin "5") (pinfunction "STDA_SSRX-_5") (pintype "bidirectional+no_connect"))
    )
    (net (code "84") (name "unconnected-(J30-STDA_SSTX+-Pad9)") (class "Default")
      (node (ref "J30") (pin "9") (pinfunction "STDA_SSTX+_9") (pintype "bidirectional+no_connect"))
    )
    (net (code "85") (name "unconnected-(J30-STDA_SSTX--Pad8)") (class "Default")
      (node (ref "J30") (pin "8") (pinfunction "STDA_SSTX-_8") (pintype "bidirectional+no_connect"))
    )
  )
)
